# Ex_Protection.net
KiCad netlist of a schematic drawn in EAGLE
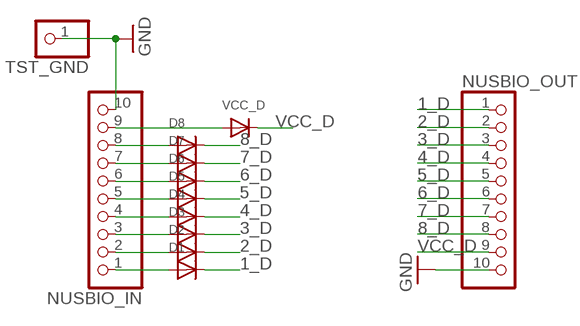
[diagram p0: schematic, sheet 1]

(export (version "E")
  (design (tool "Eeschema 10.0.6"))
  (components
    (comp (ref "D1")
      (value "DIODESOD-123")
      (footprint "eagle-import:SOD-123")
      (libsource (lib "eagle-import") (part "DIODESOD-123"))
    )
    (comp (ref "D2")
      (value "DIODESOD-123")
      (footprint "eagle-import:SOD-123")
      (libsource (lib "eagle-import") (part "DIODESOD-123"))
    )
    (comp (ref "D3")
      (value "DIODESOD-123")
      (footprint "eagle-import:SOD-123")
      (libsource (lib "eagle-import") (part "DIODESOD-123"))
    )
    (comp (ref "D4")
      (value "DIODESOD-123")
      (footprint "eagle-import:SOD-123")
      (libsource (lib "eagle-import") (part "DIODESOD-123"))
    )
    (comp (ref "D5")
      (value "DIODESOD-123")
      (footprint "eagle-import:SOD-123")
      (libsource (lib "eagle-import") (part "DIODESOD-123"))
    )
    (comp (ref "D6")
      (value "DIODESOD-123")
      (footprint "eagle-import:SOD-123")
      (libsource (lib "eagle-import") (part "DIODESOD-123"))
    )
    (comp (ref "D7")
      (value "DIODESOD-123")
      (footprint "eagle-import:SOD-123")
      (libsource (lib "eagle-import") (part "DIODESOD-123"))
    )
    (comp (ref "D8")
      (value "DIODESOD-123")
      (footprint "eagle-import:SOD-123")
      (libsource (lib "eagle-import") (part "DIODESOD-123"))
    )
    (comp (ref "NUSBIO_IN")
      (value "PINHD-1X10")
      (footprint "eagle-import:1X10-BIG")
      (libsource (lib "eagle-import") (part "PINHD-1X10"))
    )
    (comp (ref "NUSBIO_OUT")
      (value "PINHD-1X10")
      (footprint "eagle-import:1X10-BIG")
      (libsource (lib "eagle-import") (part "PINHD-1X10"))
    )
    (comp (ref "TST_GND")
      (value "PINHD-1X1")
      (footprint "eagle-import:1X01")
      (libsource (lib "eagle-import") (part "PINHD-1X1"))
    )
    (comp (ref "VCC_D")
      (value "DIODESOD-123")
      (footprint "eagle-import:SOD-123")
      (libsource (lib "eagle-import") (part "DIODESOD-123"))
    )
  )
  (nets
    (net (code "1") (name "/1_D") (class "Default")
      (node (ref "D1") (pin "C") (pinfunction "C_C") (pintype "passive"))
      (node (ref "NUSBIO_OUT") (pin "1") (pinfunction "1_1") (pintype "passive"))
    )
    (net (code "2") (name "/2_D") (class "Default")
      (node (ref "D2") (pin "C") (pinfunction "C_C") (pintype "passive"))
      (node (ref "NUSBIO_OUT") (pin "2") (pinfunction "2_2") (pintype "passive"))
    )
    (net (code "3") (name "/3_D") (class "Default")
      (node (ref "D3") (pin "C") (pinfunction "C_C") (pintype "passive"))
      (node (ref "NUSBIO_OUT") (pin "3") (pinfunction "3_3") (pintype "passive"))
    )
    (net (code "4") (name "/4_D") (class "Default")
      (node (ref "D4") (pin "C") (pinfunction "C_C") (pintype "passive"))
      (node (ref "NUSBIO_OUT") (pin "4") (pinfunction "4_4") (pintype "passive"))
    )
    (net (code "5") (name "/5_D") (class "Default")
      (node (ref "D5") (pin "C") (pinfunction "C_C") (pintype "passive"))
      (node (ref "NUSBIO_OUT") (pin "5") (pinfunction "5_5") (pintype "passive"))
    )
    (net (code "6") (name "/6_D") (class "Default")
      (node (ref "D6") (pin "C") (pinfunction "C_C") (pintype "passive"))
      (node (ref "NUSBIO_OUT") (pin "6") (pinfunction "6_6") (pintype "passive"))
    )
    (net (code "7") (name "/7_D") (class "Default")
      (node (ref "D7") (pin "C") (pinfunction "C_C") (pintype "passive"))
      (node (ref "NUSBIO_OUT") (pin "7") (pinfunction "7_7") (pintype "passive"))
    )
    (net (code "8") (name "/8_D") (class "Default")
      (node (ref "D8") (pin "C") (pinfunction "C_C") (pintype "passive"))
      (node (ref "NUSBIO_OUT") (pin "8") (pinfunction "8_8") (pintype "passive"))
    )
    (net (code "9") (name "/VCC_D") (class "Default")
      (node (ref "NUSBIO_OUT") (pin "9") (pinfunction "9_9") (pintype "passive"))
      (node (ref "VCC_D") (pin "C") (pinfunction "C_C") (pintype "passive"))
    )
    (net (code "10") (name "GND") (class "Default")
      (node (ref "NUSBIO_IN") (pin "10") (pinfunction "10_10") (pintype "passive"))
      (node (ref "NUSBIO_OUT") (pin "10") (pinfunction "10_10") (pintype "passive"))
      (node (ref "TST_GND") (pin "1") (pinfunction "1_1") (pintype "passive"))
    )
    (net (code "11") (name "Net-(D1-PadA)") (class "Default")
      (node (ref "D1") (pin "A") (pinfunction "A_A") (pintype "passive"))
      (node (ref "NUSBIO_IN") (pin "1") (pinfunction "1_1") (pintype "passive"))
    )
    (net (code "12") (name "Net-(D2-PadA)") (class "Default")
      (node (ref "D2") (pin "A") (pinfunction "A_A") (pintype "passive"))
      (node (ref "NUSBIO_IN") (pin "2") (pinfunction "2_2") (pintype "passive"))
    )
    (net (code "13") (name "Net-(D3-PadA)") (class "Default")
      (node (ref "D3") (pin "A") (pinfunction "A_A") (pintype "passive"))
      (node (ref "NUSBIO_IN") (pin "3") (pinfunction "3_3") (pintype "passive"))
    )
    (net (code "14") (name "Net-(D4-PadA)") (class "Default")
      (node (ref "D4") (pin "A") (pinfunction "A_A") (pintype "passive"))
      (node (ref "NUSBIO_IN") (pin "4") (pinfunction "4_4") (pintype "passive"))
    )
    (net (code "15") (name "Net-(D5-PadA)") (class "Default")
      (node (ref "D5") (pin "A") (pinfunction "A_A") (pintype "passive"))
      (node (ref "NUSBIO_IN") (pin "5") (pinfunction "5_5") (pintype "passive"))
    )
    (net (code "16") (name "Net-(D6-PadA)") (class "Default")
      (node (ref "D6") (pin "A") (pinfunction "A_A") (pintype "passive"))
      (node (ref "NUSBIO_IN") (pin "6") (pinfunction "6_6") (pintype "passive"))
    )
    (net (code "17") (name "Net-(D7-PadA)") (class "Default")
      (node (ref "D7") (pin "A") (pinfunction "A_A") (pintype "passive"))
      (node (ref "NUSBIO_IN") (pin "7") (pinfunction "7_7") (pintype "passive"))
    )
    (net (code "18") (name "Net-(D8-PadA)") (class "Default")
      (node (ref "D8") (pin "A") (pinfunction "A_A") (pintype "passive"))
      (node (ref "NUSBIO_IN") (pin "8") (pinfunction "8_8") (pintype "passive"))
    )
    (net (code "19") (name "Net-(NUSBIO_IN-Pad9)") (class "Default")
      (node (ref "NUSBIO_IN") (pin "9") (pinfunction "9_9") (pintype "passive"))
      (node (ref "VCC_D") (pin "A") (pinfunction "A_A") (pintype "passive"))
    )
  )
)
